# ai.net
KiCad netlist of a schematic drawn in Altium Designer
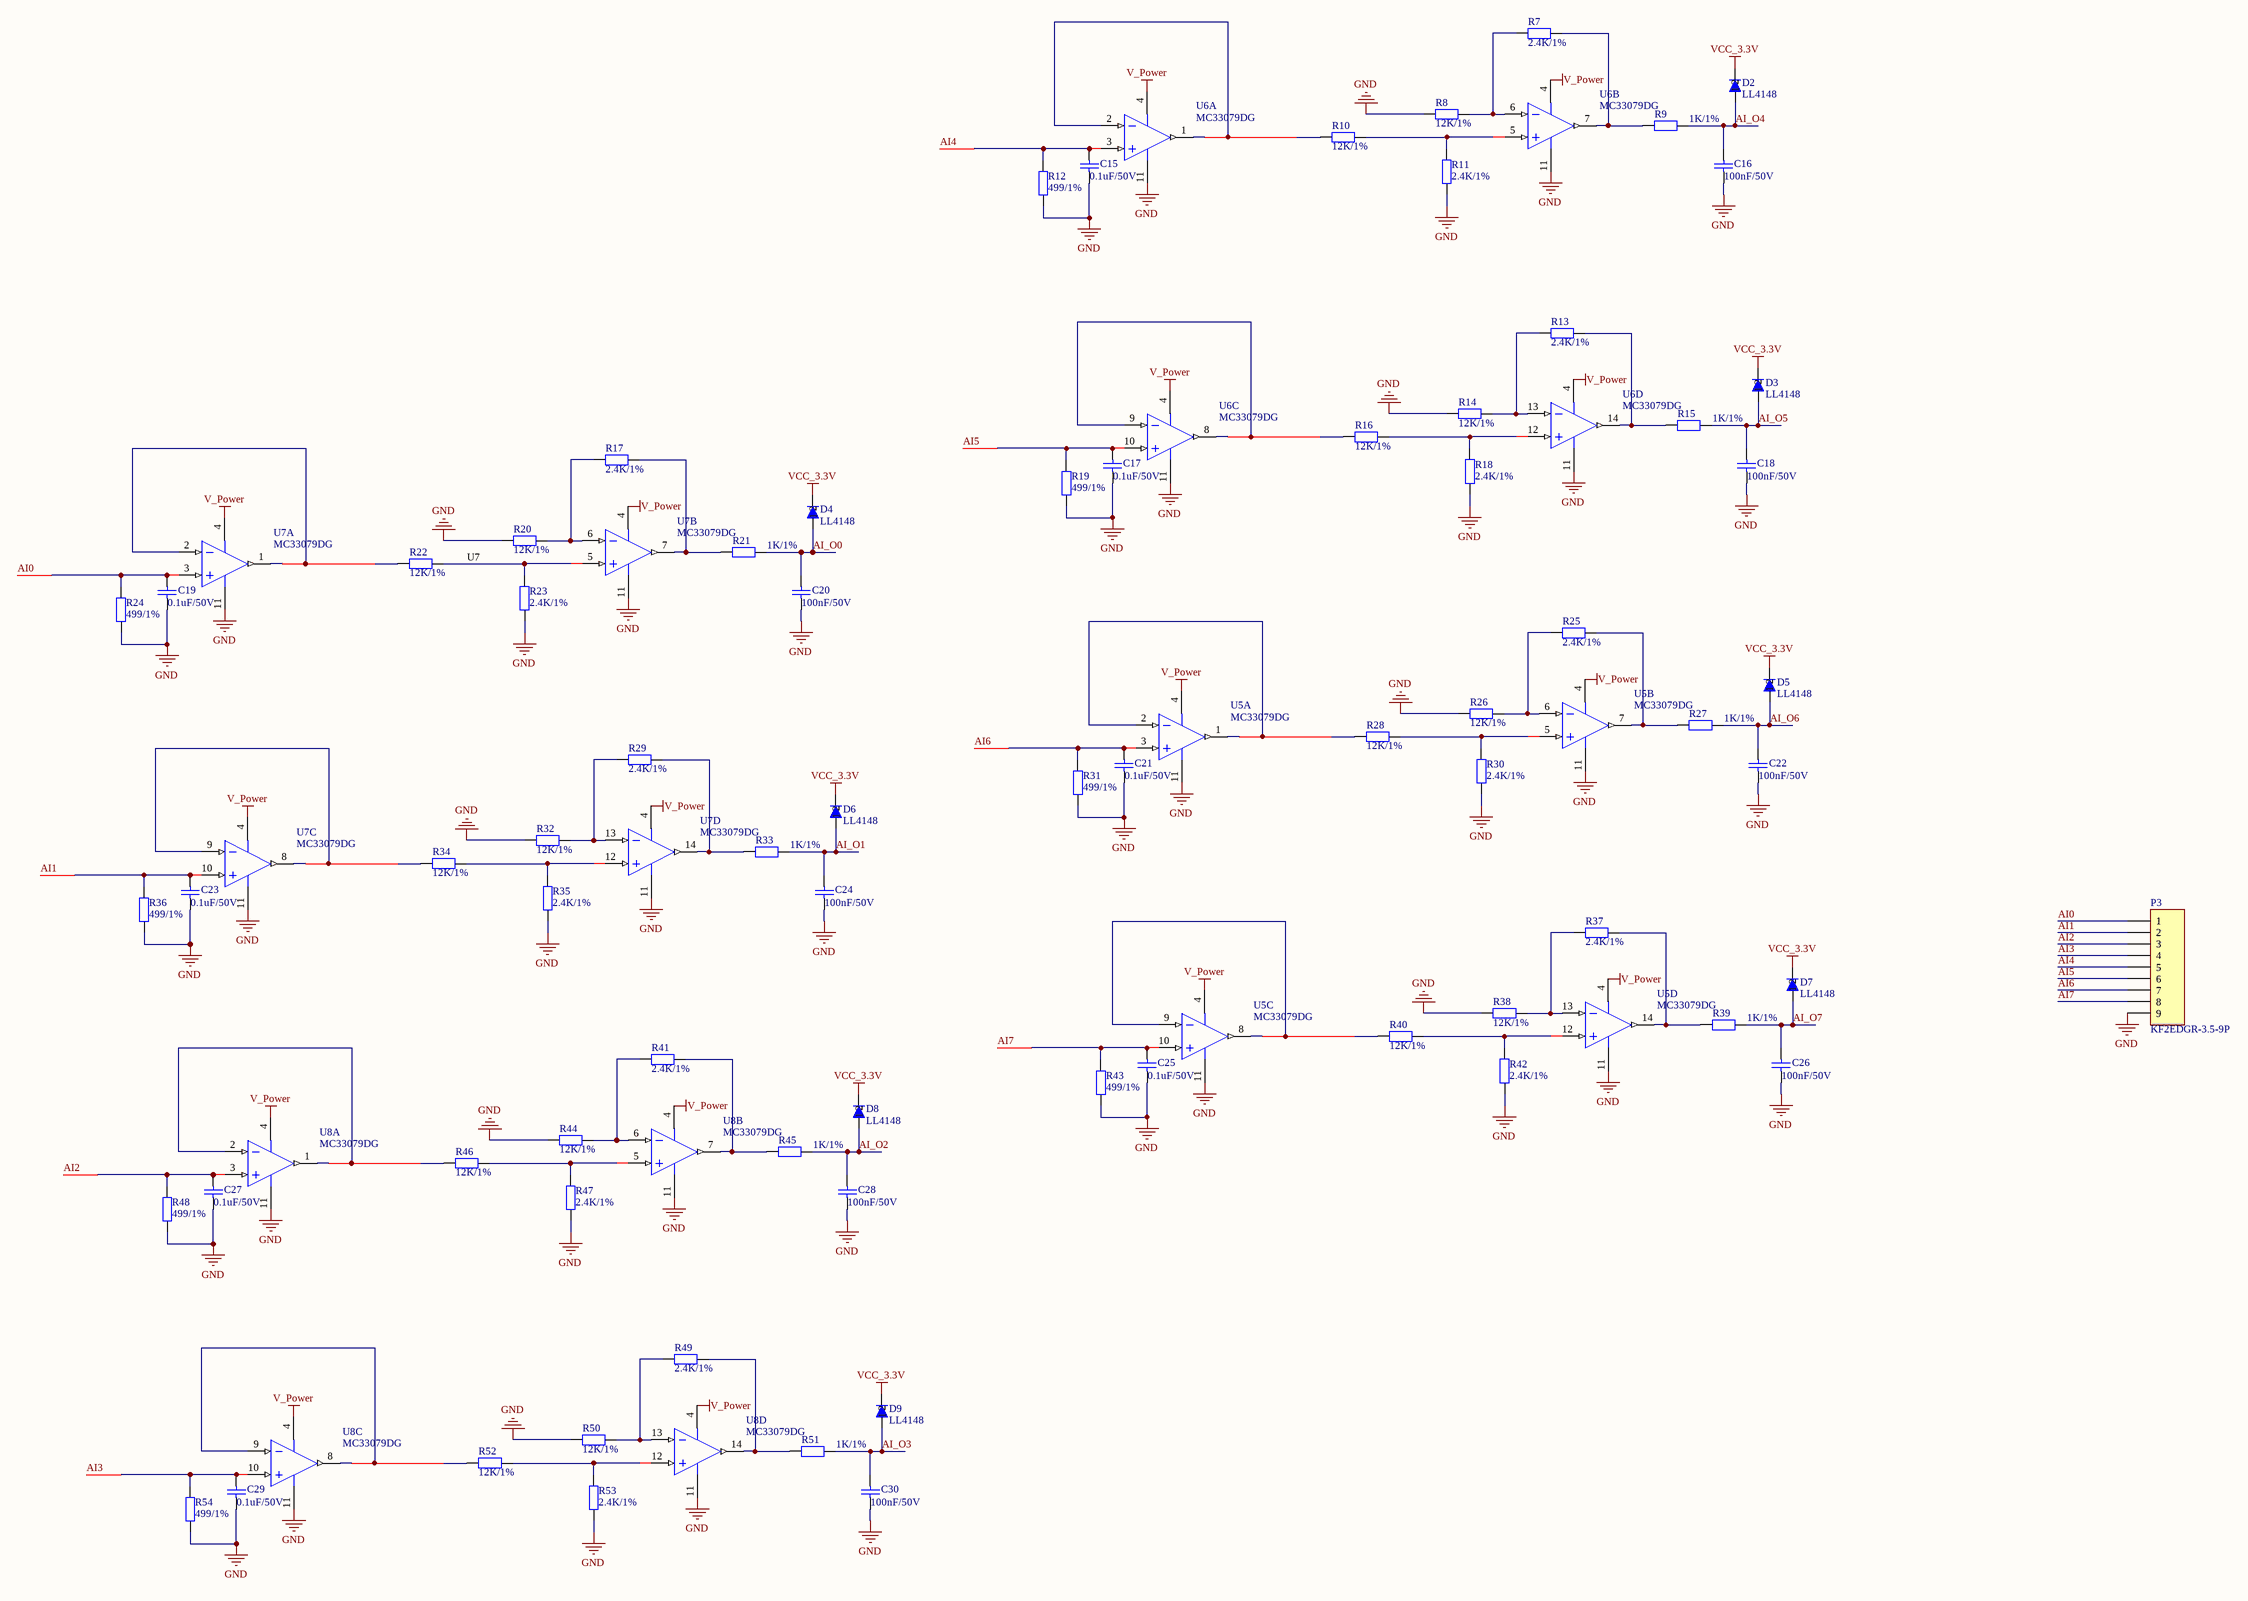
[diagram p0: ai.SchDoc]

(export (version "E")
  (design (tool "Eeschema 10.0.6"))
  (components
    (comp (ref "C15")
      (value "0.1uF/50V")
      (footprint "0603C")
      (description "Capacitor")
      (libsource (lib "Miscellaneous Devices") (part "Cap"))
    )
    (comp (ref "C16")
      (value "100nF/50V")
      (footprint "0603C")
      (description "Capacitor")
      (libsource (lib "Miscellaneous Devices") (part "Cap"))
    )
    (comp (ref "C17")
      (value "0.1uF/50V")
      (footprint "0603C")
      (description "Capacitor")
      (libsource (lib "Miscellaneous Devices") (part "Cap"))
    )
    (comp (ref "C18")
      (value "100nF/50V")
      (footprint "0603C")
      (description "Capacitor")
      (libsource (lib "Miscellaneous Devices") (part "Cap"))
    )
    (comp (ref "C19")
      (value "0.1uF/50V")
      (footprint "0603C")
      (description "Capacitor")
      (libsource (lib "Miscellaneous Devices") (part "Cap"))
    )
    (comp (ref "C20")
      (value "100nF/50V")
      (footprint "0603C")
      (description "Capacitor")
      (libsource (lib "Miscellaneous Devices") (part "Cap"))
    )
    (comp (ref "C21")
      (value "0.1uF/50V")
      (footprint "0603C")
      (description "Capacitor")
      (libsource (lib "Miscellaneous Devices") (part "Cap"))
    )
    (comp (ref "C22")
      (value "100nF/50V")
      (footprint "0603C")
      (description "Capacitor")
      (libsource (lib "Miscellaneous Devices") (part "Cap"))
    )
    (comp (ref "C23")
      (value "0.1uF/50V")
      (footprint "0603C")
      (description "Capacitor")
      (libsource (lib "Miscellaneous Devices") (part "Cap"))
    )
    (comp (ref "C24")
      (value "100nF/50V")
      (footprint "0603C")
      (description "Capacitor")
      (libsource (lib "Miscellaneous Devices") (part "Cap"))
    )
    (comp (ref "C25")
      (value "0.1uF/50V")
      (footprint "0603C")
      (description "Capacitor")
      (libsource (lib "Miscellaneous Devices") (part "Cap"))
    )
    (comp (ref "C26")
      (value "100nF/50V")
      (footprint "0603C")
      (description "Capacitor")
      (libsource (lib "Miscellaneous Devices") (part "Cap"))
    )
    (comp (ref "C27")
      (value "0.1uF/50V")
      (footprint "0603C")
      (description "Capacitor")
      (libsource (lib "Miscellaneous Devices") (part "Cap"))
    )
    (comp (ref "C28")
      (value "100nF/50V")
      (footprint "0603C")
      (description "Capacitor")
      (libsource (lib "Miscellaneous Devices") (part "Cap"))
    )
    (comp (ref "C29")
      (value "0.1uF/50V")
      (footprint "0603C")
      (description "Capacitor")
      (libsource (lib "Miscellaneous Devices") (part "Cap"))
    )
    (comp (ref "C30")
      (value "100nF/50V")
      (footprint "0603C")
      (description "Capacitor")
      (libsource (lib "Miscellaneous Devices") (part "Cap"))
    )
    (comp (ref "D2")
      (value "LL4148")
      (footprint "DO-213AB/LL34/MiniMELF")
      (description "VISHAY,LL4148,圆柱体MiniMELF100V/2A,ROHS")
      (libsource (lib "Device2018") (part "LL4148"))
    )
    (comp (ref "D3")
      (value "LL4148")
      (footprint "DO-213AB/LL34/MiniMELF")
      (description "VISHAY,LL4148,圆柱体MiniMELF100V/2A,ROHS")
      (libsource (lib "Device2018") (part "LL4148"))
    )
    (comp (ref "D4")
      (value "LL4148")
      (footprint "DO-213AB/LL34/MiniMELF")
      (description "VISHAY,LL4148,圆柱体MiniMELF100V/2A,ROHS")
      (libsource (lib "Device2018") (part "LL4148"))
    )
    (comp (ref "D5")
      (value "LL4148")
      (footprint "DO-213AB/LL34/MiniMELF")
      (description "VISHAY,LL4148,圆柱体MiniMELF100V/2A,ROHS")
      (libsource (lib "Device2018") (part "LL4148"))
    )
    (comp (ref "D6")
      (value "LL4148")
      (footprint "DO-213AB/LL34/MiniMELF")
      (description "VISHAY,LL4148,圆柱体MiniMELF100V/2A,ROHS")
      (libsource (lib "Device2018") (part "LL4148"))
    )
    (comp (ref "D7")
      (value "LL4148")
      (footprint "DO-213AB/LL34/MiniMELF")
      (description "VISHAY,LL4148,圆柱体MiniMELF100V/2A,ROHS")
      (libsource (lib "Device2018") (part "LL4148"))
    )
    (comp (ref "D8")
      (value "LL4148")
      (footprint "DO-213AB/LL34/MiniMELF")
      (description "VISHAY,LL4148,圆柱体MiniMELF100V/2A,ROHS")
      (libsource (lib "Device2018") (part "LL4148"))
    )
    (comp (ref "D9")
      (value "LL4148")
      (footprint "DO-213AB/LL34/MiniMELF")
      (description "VISHAY,LL4148,圆柱体MiniMELF100V/2A,ROHS")
      (libsource (lib "Device2018") (part "LL4148"))
    )
    (comp (ref "P3")
      (value "KF2EDGR-3.5-9P")
      (footprint "CONN-TH_9P-P3.50_KF2EDGR-3.5-9P:CONN-TH_9P-P3.50_KF2EDGR-3.5-9P")
      (description "Header, 9-Pin")
      (libsource (lib "Miscellaneous Connectors") (part "Header 9"))
    )
    (comp (ref "R7") (value "2.4K/1%") (footprint "0603R") (libsource (lib "") (part "Res0805M_1")))
    (comp (ref "R8") (value "12K/1%") (footprint "0603R") (libsource (lib "") (part "Res0805M_1")))
    (comp (ref "R9") (value "1K/1%") (footprint "0603R") (libsource (lib "") (part "Res0805M_1")))
    (comp (ref "R10") (value "12K/1%") (footprint "0603R") (libsource (lib "") (part "Res0805M_1")))
    (comp (ref "R11") (value "2.4K/1%") (footprint "0603R") (libsource (lib "MQlibrary") (part "Res0805M")))
    (comp (ref "R12") (value "499/1%") (footprint "0603R") (libsource (lib "MQlibrary") (part "Res0805M")))
    (comp (ref "R13") (value "2.4K/1%") (footprint "0603R") (libsource (lib "") (part "Res0805M_1")))
    (comp (ref "R14") (value "12K/1%") (footprint "0603R") (libsource (lib "") (part "Res0805M_1")))
    (comp (ref "R15") (value "1K/1%") (footprint "0603R") (libsource (lib "") (part "Res0805M_1")))
    (comp (ref "R16") (value "12K/1%") (footprint "0603R") (libsource (lib "") (part "Res0805M_1")))
    (comp (ref "R17") (value "2.4K/1%") (footprint "0603R") (libsource (lib "") (part "Res0805M_1")))
    (comp (ref "R18") (value "2.4K/1%") (footprint "0603R") (libsource (lib "MQlibrary") (part "Res0805M")))
    (comp (ref "R19") (value "499/1%") (footprint "0603R") (libsource (lib "MQlibrary") (part "Res0805M")))
    (comp (ref "R20") (value "12K/1%") (footprint "0603R") (libsource (lib "") (part "Res0805M_1")))
    (comp (ref "R21") (value "1K/1%") (footprint "0603R") (libsource (lib "") (part "Res0805M_1")))
    (comp (ref "R22") (value "12K/1%") (footprint "0603R") (libsource (lib "") (part "Res0805M_1")))
    (comp (ref "R23") (value "2.4K/1%") (footprint "0603R") (libsource (lib "MQlibrary") (part "Res0805M")))
    (comp (ref "R24") (value "499/1%") (footprint "0603R") (libsource (lib "MQlibrary") (part "Res0805M")))
    (comp (ref "R25") (value "2.4K/1%") (footprint "0603R") (libsource (lib "") (part "Res0805M_1")))
    (comp (ref "R26") (value "12K/1%") (footprint "0603R") (libsource (lib "") (part "Res0805M_1")))
    (comp (ref "R27") (value "1K/1%") (footprint "0603R") (libsource (lib "") (part "Res0805M_1")))
    (comp (ref "R28") (value "12K/1%") (footprint "0603R") (libsource (lib "") (part "Res0805M_1")))
    (comp (ref "R29") (value "2.4K/1%") (footprint "0603R") (libsource (lib "") (part "Res0805M_1")))
    (comp (ref "R30") (value "2.4K/1%") (footprint "0603R") (libsource (lib "MQlibrary") (part "Res0805M")))
    (comp (ref "R31") (value "499/1%") (footprint "0603R") (libsource (lib "MQlibrary") (part "Res0805M")))
    (comp (ref "R32") (value "12K/1%") (footprint "0603R") (libsource (lib "") (part "Res0805M_1")))
    (comp (ref "R33") (value "1K/1%") (footprint "0603R") (libsource (lib "") (part "Res0805M_1")))
    (comp (ref "R34") (value "12K/1%") (footprint "0603R") (libsource (lib "") (part "Res0805M_1")))
    (comp (ref "R35") (value "2.4K/1%") (footprint "0603R") (libsource (lib "MQlibrary") (part "Res0805M")))
    (comp (ref "R36") (value "499/1%") (footprint "0603R") (libsource (lib "MQlibrary") (part "Res0805M")))
    (comp (ref "R37") (value "2.4K/1%") (footprint "0603R") (libsource (lib "") (part "Res0805M_1")))
    (comp (ref "R38") (value "12K/1%") (footprint "0603R") (libsource (lib "") (part "Res0805M_1")))
    (comp (ref "R39") (value "1K/1%") (footprint "0603R") (libsource (lib "") (part "Res0805M_1")))
    (comp (ref "R40") (value "12K/1%") (footprint "0603R") (libsource (lib "") (part "Res0805M_1")))
    (comp (ref "R41") (value "2.4K/1%") (footprint "0603R") (libsource (lib "") (part "Res0805M_1")))
    (comp (ref "R42") (value "2.4K/1%") (footprint "0603R") (libsource (lib "MQlibrary") (part "Res0805M")))
    (comp (ref "R43") (value "499/1%") (footprint "0603R") (libsource (lib "MQlibrary") (part "Res0805M")))
    (comp (ref "R44") (value "12K/1%") (footprint "0603R") (libsource (lib "") (part "Res0805M_1")))
    (comp (ref "R45") (value "1K/1%") (footprint "0603R") (libsource (lib "") (part "Res0805M_1")))
    (comp (ref "R46") (value "12K/1%") (footprint "0603R") (libsource (lib "") (part "Res0805M_1")))
    (comp (ref "R47") (value "2.4K/1%") (footprint "0603R") (libsource (lib "MQlibrary") (part "Res0805M")))
    (comp (ref "R48") (value "499/1%") (footprint "0603R") (libsource (lib "MQlibrary") (part "Res0805M")))
    (comp (ref "R49") (value "2.4K/1%") (footprint "0603R") (libsource (lib "") (part "Res0805M_1")))
    (comp (ref "R50") (value "12K/1%") (footprint "0603R") (libsource (lib "") (part "Res0805M_1")))
    (comp (ref "R51") (value "1K/1%") (footprint "0603R") (libsource (lib "") (part "Res0805M_1")))
    (comp (ref "R52") (value "12K/1%") (footprint "0603R") (libsource (lib "") (part "Res0805M_1")))
    (comp (ref "R53") (value "2.4K/1%") (footprint "0603R") (libsource (lib "MQlibrary") (part "Res0805M")))
    (comp (ref "R54") (value "499/1%") (footprint "0603R") (libsource (lib "MQlibrary") (part "Res0805M")))
    (comp (ref "U5")
      (value "MC33079DG")
      (footprint "SOP-14_N")
      (description "Quad High-speed, Ultra Low-power, Single-Supply TTL comparator")
      (libsource (lib "Maxim Analog Comparator") (part "MAX908EPD"))
    )
    (comp (ref "U6")
      (value "MC33079DG")
      (footprint "SOP-14_N")
      (description "Quad High-speed, Ultra Low-power, Single-Supply TTL comparator")
      (libsource (lib "Maxim Analog Comparator") (part "MAX908EPD"))
    )
    (comp (ref "U7")
      (value "MC33079DG")
      (footprint "SOP-14_N")
      (description "Quad High-speed, Ultra Low-power, Single-Supply TTL comparator")
      (libsource (lib "Maxim Analog Comparator") (part "MAX908EPD"))
    )
    (comp (ref "U8")
      (value "MC33079DG")
      (footprint "SOP-14_N")
      (description "Quad High-speed, Ultra Low-power, Single-Supply TTL comparator")
      (libsource (lib "Maxim Analog Comparator") (part "MAX908EPD"))
    )
  )
  (nets
    (net (code "1") (name "/AI0") (class "Default")
      (node (ref "C19") (pin "2") (pinfunction "2_2") (pintype "passive"))
      (node (ref "P3") (pin "1") (pinfunction "1_1") (pintype "passive"))
      (node (ref "R24") (pin "1") (pinfunction "1_1") (pintype "passive"))
      (node (ref "U7") (pin "3") (pinfunction "IN+_3") (pintype "input"))
    )
    (net (code "2") (name "/AI1") (class "Default")
      (node (ref "C23") (pin "2") (pinfunction "2_2") (pintype "passive"))
      (node (ref "P3") (pin "2") (pinfunction "2_2") (pintype "passive"))
      (node (ref "R36") (pin "1") (pinfunction "1_1") (pintype "passive"))
      (node (ref "U7") (pin "10") (pinfunction "IN+_10") (pintype "input"))
    )
    (net (code "3") (name "/AI2") (class "Default")
      (node (ref "C27") (pin "2") (pinfunction "2_2") (pintype "passive"))
      (node (ref "P3") (pin "3") (pinfunction "3_3") (pintype "passive"))
      (node (ref "R48") (pin "1") (pinfunction "1_1") (pintype "passive"))
      (node (ref "U8") (pin "3") (pinfunction "IN+_3") (pintype "input"))
    )
    (net (code "4") (name "/AI3") (class "Default")
      (node (ref "C29") (pin "2") (pinfunction "2_2") (pintype "passive"))
      (node (ref "P3") (pin "4") (pinfunction "4_4") (pintype "passive"))
      (node (ref "R54") (pin "1") (pinfunction "1_1") (pintype "passive"))
      (node (ref "U8") (pin "10") (pinfunction "IN+_10") (pintype "input"))
    )
    (net (code "5") (name "/AI4") (class "Default")
      (node (ref "C15") (pin "2") (pinfunction "2_2") (pintype "passive"))
      (node (ref "P3") (pin "5") (pinfunction "5_5") (pintype "passive"))
      (node (ref "R12") (pin "1") (pinfunction "1_1") (pintype "passive"))
      (node (ref "U6") (pin "3") (pinfunction "IN+_3") (pintype "input"))
    )
    (net (code "6") (name "/AI5") (class "Default")
      (node (ref "C17") (pin "2") (pinfunction "2_2") (pintype "passive"))
      (node (ref "P3") (pin "6") (pinfunction "6_6") (pintype "passive"))
      (node (ref "R19") (pin "1") (pinfunction "1_1") (pintype "passive"))
      (node (ref "U6") (pin "10") (pinfunction "IN+_10") (pintype "input"))
    )
    (net (code "7") (name "/AI6") (class "Default")
      (node (ref "C21") (pin "2") (pinfunction "2_2") (pintype "passive"))
      (node (ref "P3") (pin "7") (pinfunction "7_7") (pintype "passive"))
      (node (ref "R31") (pin "1") (pinfunction "1_1") (pintype "passive"))
      (node (ref "U5") (pin "3") (pinfunction "IN+_3") (pintype "input"))
    )
    (net (code "8") (name "/AI7") (class "Default")
      (node (ref "C25") (pin "2") (pinfunction "2_2") (pintype "passive"))
      (node (ref "P3") (pin "8") (pinfunction "8_8") (pintype "passive"))
      (node (ref "R43") (pin "1") (pinfunction "1_1") (pintype "passive"))
      (node (ref "U5") (pin "10") (pinfunction "IN+_10") (pintype "input"))
    )
    (net (code "9") (name "/AI_O0") (class "Default")
      (node (ref "C20") (pin "2") (pinfunction "2_2") (pintype "passive"))
      (node (ref "D4") (pin "1") (pinfunction "2_1") (pintype "passive"))
      (node (ref "R21") (pin "2") (pinfunction "2_2") (pintype "passive"))
    )
    (net (code "10") (name "/AI_O1") (class "Default")
      (node (ref "C24") (pin "2") (pinfunction "2_2") (pintype "passive"))
      (node (ref "D6") (pin "1") (pinfunction "2_1") (pintype "passive"))
      (node (ref "R33") (pin "2") (pinfunction "2_2") (pintype "passive"))
    )
    (net (code "11") (name "/AI_O2") (class "Default")
      (node (ref "C28") (pin "2") (pinfunction "2_2") (pintype "passive"))
      (node (ref "D8") (pin "1") (pinfunction "2_1") (pintype "passive"))
      (node (ref "R45") (pin "2") (pinfunction "2_2") (pintype "passive"))
    )
    (net (code "12") (name "/AI_O3") (class "Default")
      (node (ref "C30") (pin "2") (pinfunction "2_2") (pintype "passive"))
      (node (ref "D9") (pin "1") (pinfunction "2_1") (pintype "passive"))
      (node (ref "R51") (pin "2") (pinfunction "2_2") (pintype "passive"))
    )
    (net (code "13") (name "/AI_O4") (class "Default")
      (node (ref "C16") (pin "2") (pinfunction "2_2") (pintype "passive"))
      (node (ref "D2") (pin "1") (pinfunction "2_1") (pintype "passive"))
      (node (ref "R9") (pin "2") (pinfunction "2_2") (pintype "passive"))
    )
    (net (code "14") (name "/AI_O5") (class "Default")
      (node (ref "C18") (pin "2") (pinfunction "2_2") (pintype "passive"))
      (node (ref "D3") (pin "1") (pinfunction "2_1") (pintype "passive"))
      (node (ref "R15") (pin "2") (pinfunction "2_2") (pintype "passive"))
    )
    (net (code "15") (name "/AI_O6") (class "Default")
      (node (ref "C22") (pin "2") (pinfunction "2_2") (pintype "passive"))
      (node (ref "D5") (pin "1") (pinfunction "2_1") (pintype "passive"))
      (node (ref "R27") (pin "2") (pinfunction "2_2") (pintype "passive"))
    )
    (net (code "16") (name "/AI_O7") (class "Default")
      (node (ref "C26") (pin "2") (pinfunction "2_2") (pintype "passive"))
      (node (ref "D7") (pin "1") (pinfunction "2_1") (pintype "passive"))
      (node (ref "R39") (pin "2") (pinfunction "2_2") (pintype "passive"))
    )
    (net (code "17") (name "GND") (class "Default")
      (node (ref "C15") (pin "1") (pinfunction "1_1") (pintype "passive"))
      (node (ref "C16") (pin "1") (pinfunction "1_1") (pintype "passive"))
      (node (ref "C17") (pin "1") (pinfunction "1_1") (pintype "passive"))
      (node (ref "C18") (pin "1") (pinfunction "1_1") (pintype "passive"))
      (node (ref "C19") (pin "1") (pinfunction "1_1") (pintype "passive"))
      (node (ref "C20") (pin "1") (pinfunction "1_1") (pintype "passive"))
      (node (ref "C21") (pin "1") (pinfunction "1_1") (pintype "passive"))
      (node (ref "C22") (pin "1") (pinfunction "1_1") (pintype "passive"))
      (node (ref "C23") (pin "1") (pinfunction "1_1") (pintype "passive"))
      (node (ref "C24") (pin "1") (pinfunction "1_1") (pintype "passive"))
      (node (ref "C25") (pin "1") (pinfunction "1_1") (pintype "passive"))
      (node (ref "C26") (pin "1") (pinfunction "1_1") (pintype "passive"))
      (node (ref "C27") (pin "1") (pinfunction "1_1") (pintype "passive"))
      (node (ref "C28") (pin "1") (pinfunction "1_1") (pintype "passive"))
      (node (ref "C29") (pin "1") (pinfunction "1_1") (pintype "passive"))
      (node (ref "C30") (pin "1") (pinfunction "1_1") (pintype "passive"))
      (node (ref "P3") (pin "9") (pinfunction "9_9") (pintype "passive"))
      (node (ref "R11") (pin "2") (pinfunction "2_2") (pintype "passive"))
      (node (ref "R12") (pin "2") (pinfunction "2_2") (pintype "passive"))
      (node (ref "R14") (pin "1") (pinfunction "1_1") (pintype "passive"))
      (node (ref "R18") (pin "2") (pinfunction "2_2") (pintype "passive"))
      (node (ref "R19") (pin "2") (pinfunction "2_2") (pintype "passive"))
      (node (ref "R20") (pin "1") (pinfunction "1_1") (pintype "passive"))
      (node (ref "R23") (pin "2") (pinfunction "2_2") (pintype "passive"))
      (node (ref "R24") (pin "2") (pinfunction "2_2") (pintype "passive"))
      (node (ref "R26") (pin "1") (pinfunction "1_1") (pintype "passive"))
      (node (ref "R30") (pin "2") (pinfunction "2_2") (pintype "passive"))
      (node (ref "R31") (pin "2") (pinfunction "2_2") (pintype "passive"))
      (node (ref "R32") (pin "1") (pinfunction "1_1") (pintype "passive"))
      (node (ref "R35") (pin "2") (pinfunction "2_2") (pintype "passive"))
      (node (ref "R36") (pin "2") (pinfunction "2_2") (pintype "passive"))
      (node (ref "R38") (pin "1") (pinfunction "1_1") (pintype "passive"))
      (node (ref "R42") (pin "2") (pinfunction "2_2") (pintype "passive"))
      (node (ref "R43") (pin "2") (pinfunction "2_2") (pintype "passive"))
      (node (ref "R44") (pin "1") (pinfunction "1_1") (pintype "passive"))
      (node (ref "R47") (pin "2") (pinfunction "2_2") (pintype "passive"))
      (node (ref "R48") (pin "2") (pinfunction "2_2") (pintype "passive"))
      (node (ref "R50") (pin "1") (pinfunction "1_1") (pintype "passive"))
      (node (ref "R53") (pin "2") (pinfunction "2_2") (pintype "passive"))
      (node (ref "R54") (pin "2") (pinfunction "2_2") (pintype "passive"))
      (node (ref "R8") (pin "1") (pinfunction "1_1") (pintype "passive"))
      (node (ref "U5") (pin "11") (pinfunction "GND_11") (pintype "power_in"))
      (node (ref "U6") (pin "11") (pinfunction "GND_11") (pintype "power_in"))
      (node (ref "U7") (pin "11") (pinfunction "GND_11") (pintype "power_in"))
      (node (ref "U8") (pin "11") (pinfunction "GND_11") (pintype "power_in"))
    )
    (net (code "18") (name "Net-(U5A-IN-)") (class "Default")
      (node (ref "R28") (pin "1") (pinfunction "1_1") (pintype "passive"))
      (node (ref "U5") (pin "1") (pinfunction "OUT_1") (pintype "output"))
      (node (ref "U5") (pin "2") (pinfunction "IN-_2") (pintype "input"))
    )
    (net (code "19") (name "Net-(U5B-IN+)") (class "Default")
      (node (ref "R28") (pin "2") (pinfunction "2_2") (pintype "passive"))
      (node (ref "R30") (pin "1") (pinfunction "1_1") (pintype "passive"))
      (node (ref "U5") (pin "5") (pinfunction "IN+_5") (pintype "input"))
    )
    (net (code "20") (name "Net-(U5B-IN-)") (class "Default")
      (node (ref "R25") (pin "1") (pinfunction "1_1") (pintype "passive"))
      (node (ref "R26") (pin "2") (pinfunction "2_2") (pintype "passive"))
      (node (ref "U5") (pin "6") (pinfunction "IN-_6") (pintype "input"))
    )
    (net (code "21") (name "Net-(U5B-OUT)") (class "Default")
      (node (ref "R25") (pin "2") (pinfunction "2_2") (pintype "passive"))
      (node (ref "R27") (pin "1") (pinfunction "1_1") (pintype "passive"))
      (node (ref "U5") (pin "7") (pinfunction "OUT_7") (pintype "output"))
    )
    (net (code "22") (name "Net-(U5C-IN-)") (class "Default")
      (node (ref "R40") (pin "1") (pinfunction "1_1") (pintype "passive"))
      (node (ref "U5") (pin "8") (pinfunction "OUT_8") (pintype "output"))
      (node (ref "U5") (pin "9") (pinfunction "IN-_9") (pintype "input"))
    )
    (net (code "23") (name "Net-(U5D-IN+)") (class "Default")
      (node (ref "R40") (pin "2") (pinfunction "2_2") (pintype "passive"))
      (node (ref "R42") (pin "1") (pinfunction "1_1") (pintype "passive"))
      (node (ref "U5") (pin "12") (pinfunction "IN+_12") (pintype "input"))
    )
    (net (code "24") (name "Net-(U5D-IN-)") (class "Default")
      (node (ref "R37") (pin "1") (pinfunction "1_1") (pintype "passive"))
      (node (ref "R38") (pin "2") (pinfunction "2_2") (pintype "passive"))
      (node (ref "U5") (pin "13") (pinfunction "IN-_13") (pintype "input"))
    )
    (net (code "25") (name "Net-(U5D-OUT)") (class "Default")
      (node (ref "R37") (pin "2") (pinfunction "2_2") (pintype "passive"))
      (node (ref "R39") (pin "1") (pinfunction "1_1") (pintype "passive"))
      (node (ref "U5") (pin "14") (pinfunction "OUT_14") (pintype "output"))
    )
    (net (code "26") (name "Net-(U6A-IN-)") (class "Default")
      (node (ref "R10") (pin "1") (pinfunction "1_1") (pintype "passive"))
      (node (ref "U6") (pin "1") (pinfunction "OUT_1") (pintype "output"))
      (node (ref "U6") (pin "2") (pinfunction "IN-_2") (pintype "input"))
    )
    (net (code "27") (name "Net-(U6B-IN+)") (class "Default")
      (node (ref "R10") (pin "2") (pinfunction "2_2") (pintype "passive"))
      (node (ref "R11") (pin "1") (pinfunction "1_1") (pintype "passive"))
      (node (ref "U6") (pin "5") (pinfunction "IN+_5") (pintype "input"))
    )
    (net (code "28") (name "Net-(U6B-IN-)") (class "Default")
      (node (ref "R7") (pin "1") (pinfunction "1_1") (pintype "passive"))
      (node (ref "R8") (pin "2") (pinfunction "2_2") (pintype "passive"))
      (node (ref "U6") (pin "6") (pinfunction "IN-_6") (pintype "input"))
    )
    (net (code "29") (name "Net-(U6B-OUT)") (class "Default")
      (node (ref "R7") (pin "2") (pinfunction "2_2") (pintype "passive"))
      (node (ref "R9") (pin "1") (pinfunction "1_1") (pintype "passive"))
      (node (ref "U6") (pin "7") (pinfunction "OUT_7") (pintype "output"))
    )
    (net (code "30") (name "Net-(U6C-IN-)") (class "Default")
      (node (ref "R16") (pin "1") (pinfunction "1_1") (pintype "passive"))
      (node (ref "U6") (pin "8") (pinfunction "OUT_8") (pintype "output"))
      (node (ref "U6") (pin "9") (pinfunction "IN-_9") (pintype "input"))
    )
    (net (code "31") (name "Net-(U6D-IN+)") (class "Default")
      (node (ref "R16") (pin "2") (pinfunction "2_2") (pintype "passive"))
      (node (ref "R18") (pin "1") (pinfunction "1_1") (pintype "passive"))
      (node (ref "U6") (pin "12") (pinfunction "IN+_12") (pintype "input"))
    )
    (net (code "32") (name "Net-(U6D-IN-)") (class "Default")
      (node (ref "R13") (pin "1") (pinfunction "1_1") (pintype "passive"))
      (node (ref "R14") (pin "2") (pinfunction "2_2") (pintype "passive"))
      (node (ref "U6") (pin "13") (pinfunction "IN-_13") (pintype "input"))
    )
    (net (code "33") (name "Net-(U6D-OUT)") (class "Default")
      (node (ref "R13") (pin "2") (pinfunction "2_2") (pintype "passive"))
      (node (ref "R15") (pin "1") (pinfunction "1_1") (pintype "passive"))
      (node (ref "U6") (pin "14") (pinfunction "OUT_14") (pintype "output"))
    )
    (net (code "34") (name "Net-(U7A-IN-)") (class "Default")
      (node (ref "R22") (pin "1") (pinfunction "1_1") (pintype "passive"))
      (node (ref "U7") (pin "1") (pinfunction "OUT_1") (pintype "output"))
      (node (ref "U7") (pin "2") (pinfunction "IN-_2") (pintype "input"))
    )
    (net (code "35") (name "Net-(U7B-IN+)") (class "Default")
      (node (ref "R22") (pin "2") (pinfunction "2_2") (pintype "passive"))
      (node (ref "R23") (pin "1") (pinfunction "1_1") (pintype "passive"))
      (node (ref "U7") (pin "5") (pinfunction "IN+_5") (pintype "input"))
    )
    (net (code "36") (name "Net-(U7B-IN-)") (class "Default")
      (node (ref "R17") (pin "1") (pinfunction "1_1") (pintype "passive"))
      (node (ref "R20") (pin "2") (pinfunction "2_2") (pintype "passive"))
      (node (ref "U7") (pin "6") (pinfunction "IN-_6") (pintype "input"))
    )
    (net (code "37") (name "Net-(U7B-OUT)") (class "Default")
      (node (ref "R17") (pin "2") (pinfunction "2_2") (pintype "passive"))
      (node (ref "R21") (pin "1") (pinfunction "1_1") (pintype "passive"))
      (node (ref "U7") (pin "7") (pinfunction "OUT_7") (pintype "output"))
    )
    (net (code "38") (name "Net-(U7C-IN-)") (class "Default")
      (node (ref "R34") (pin "1") (pinfunction "1_1") (pintype "passive"))
      (node (ref "U7") (pin "8") (pinfunction "OUT_8") (pintype "output"))
      (node (ref "U7") (pin "9") (pinfunction "IN-_9") (pintype "input"))
    )
    (net (code "39") (name "Net-(U7D-IN+)") (class "Default")
      (node (ref "R34") (pin "2") (pinfunction "2_2") (pintype "passive"))
      (node (ref "R35") (pin "1") (pinfunction "1_1") (pintype "passive"))
      (node (ref "U7") (pin "12") (pinfunction "IN+_12") (pintype "input"))
    )
    (net (code "40") (name "Net-(U7D-IN-)") (class "Default")
      (node (ref "R29") (pin "1") (pinfunction "1_1") (pintype "passive"))
      (node (ref "R32") (pin "2") (pinfunction "2_2") (pintype "passive"))
      (node (ref "U7") (pin "13") (pinfunction "IN-_13") (pintype "input"))
    )
    (net (code "41") (name "Net-(U7D-OUT)") (class "Default")
      (node (ref "R29") (pin "2") (pinfunction "2_2") (pintype "passive"))
      (node (ref "R33") (pin "1") (pinfunction "1_1") (pintype "passive"))
      (node (ref "U7") (pin "14") (pinfunction "OUT_14") (pintype "output"))
    )
    (net (code "42") (name "Net-(U8A-IN-)") (class "Default")
      (node (ref "R46") (pin "1") (pinfunction "1_1") (pintype "passive"))
      (node (ref "U8") (pin "1") (pinfunction "OUT_1") (pintype "output"))
      (node (ref "U8") (pin "2") (pinfunction "IN-_2") (pintype "input"))
    )
    (net (code "43") (name "Net-(U8B-IN+)") (class "Default")
      (node (ref "R46") (pin "2") (pinfunction "2_2") (pintype "passive"))
      (node (ref "R47") (pin "1") (pinfunction "1_1") (pintype "passive"))
      (node (ref "U8") (pin "5") (pinfunction "IN+_5") (pintype "input"))
    )
    (net (code "44") (name "Net-(U8B-IN-)") (class "Default")
      (node (ref "R41") (pin "1") (pinfunction "1_1") (pintype "passive"))
      (node (ref "R44") (pin "2") (pinfunction "2_2") (pintype "passive"))
      (node (ref "U8") (pin "6") (pinfunction "IN-_6") (pintype "input"))
    )
    (net (code "45") (name "Net-(U8B-OUT)") (class "Default")
      (node (ref "R41") (pin "2") (pinfunction "2_2") (pintype "passive"))
      (node (ref "R45") (pin "1") (pinfunction "1_1") (pintype "passive"))
      (node (ref "U8") (pin "7") (pinfunction "OUT_7") (pintype "output"))
    )
    (net (code "46") (name "Net-(U8C-IN-)") (class "Default")
      (node (ref "R52") (pin "1") (pinfunction "1_1") (pintype "passive"))
      (node (ref "U8") (pin "8") (pinfunction "OUT_8") (pintype "output"))
      (node (ref "U8") (pin "9") (pinfunction "IN-_9") (pintype "input"))
    )
    (net (code "47") (name "Net-(U8D-IN+)") (class "Default")
      (node (ref "R52") (pin "2") (pinfunction "2_2") (pintype "passive"))
      (node (ref "R53") (pin "1") (pinfunction "1_1") (pintype "passive"))
      (node (ref "U8") (pin "12") (pinfunction "IN+_12") (pintype "input"))
    )
    (net (code "48") (name "Net-(U8D-IN-)") (class "Default")
      (node (ref "R49") (pin "1") (pinfunction "1_1") (pintype "passive"))
      (node (ref "R50") (pin "2") (pinfunction "2_2") (pintype "passive"))
      (node (ref "U8") (pin "13") (pinfunction "IN-_13") (pintype "input"))
    )
    (net (code "49") (name "Net-(U8D-OUT)") (class "Default")
      (node (ref "R49") (pin "2") (pinfunction "2_2") (pintype "passive"))
      (node (ref "R51") (pin "1") (pinfunction "1_1") (pintype "passive"))
      (node (ref "U8") (pin "14") (pinfunction "OUT_14") (pintype "output"))
    )
    (net (code "50") (name "VCC_3.3V") (class "Default")
      (node (ref "D2") (pin "2") (pinfunction "1_2") (pintype "passive"))
      (node (ref "D3") (pin "2") (pinfunction "1_2") (pintype "passive"))
      (node (ref "D4") (pin "2") (pinfunction "1_2") (pintype "passive"))
      (node (ref "D5") (pin "2") (pinfunction "1_2") (pintype "passive"))
      (node (ref "D6") (pin "2") (pinfunction "1_2") (pintype "passive"))
      (node (ref "D7") (pin "2") (pinfunction "1_2") (pintype "passive"))
      (node (ref "D8") (pin "2") (pinfunction "1_2") (pintype "passive"))
      (node (ref "D9") (pin "2") (pinfunction "1_2") (pintype "passive"))
    )
    (net (code "51") (name "V_Power") (class "Default")
      (node (ref "U5") (pin "4") (pinfunction "V+_4") (pintype "power_in"))
      (node (ref "U6") (pin "4") (pinfunction "V+_4") (pintype "power_in"))
      (node (ref "U7") (pin "4") (pinfunction "V+_4") (pintype "power_in"))
      (node (ref "U8") (pin "4") (pinfunction "V+_4") (pintype "power_in"))
    )
  )
)
